# Sheet.net
KiCad netlist of a schematic drawn in Altium Designer
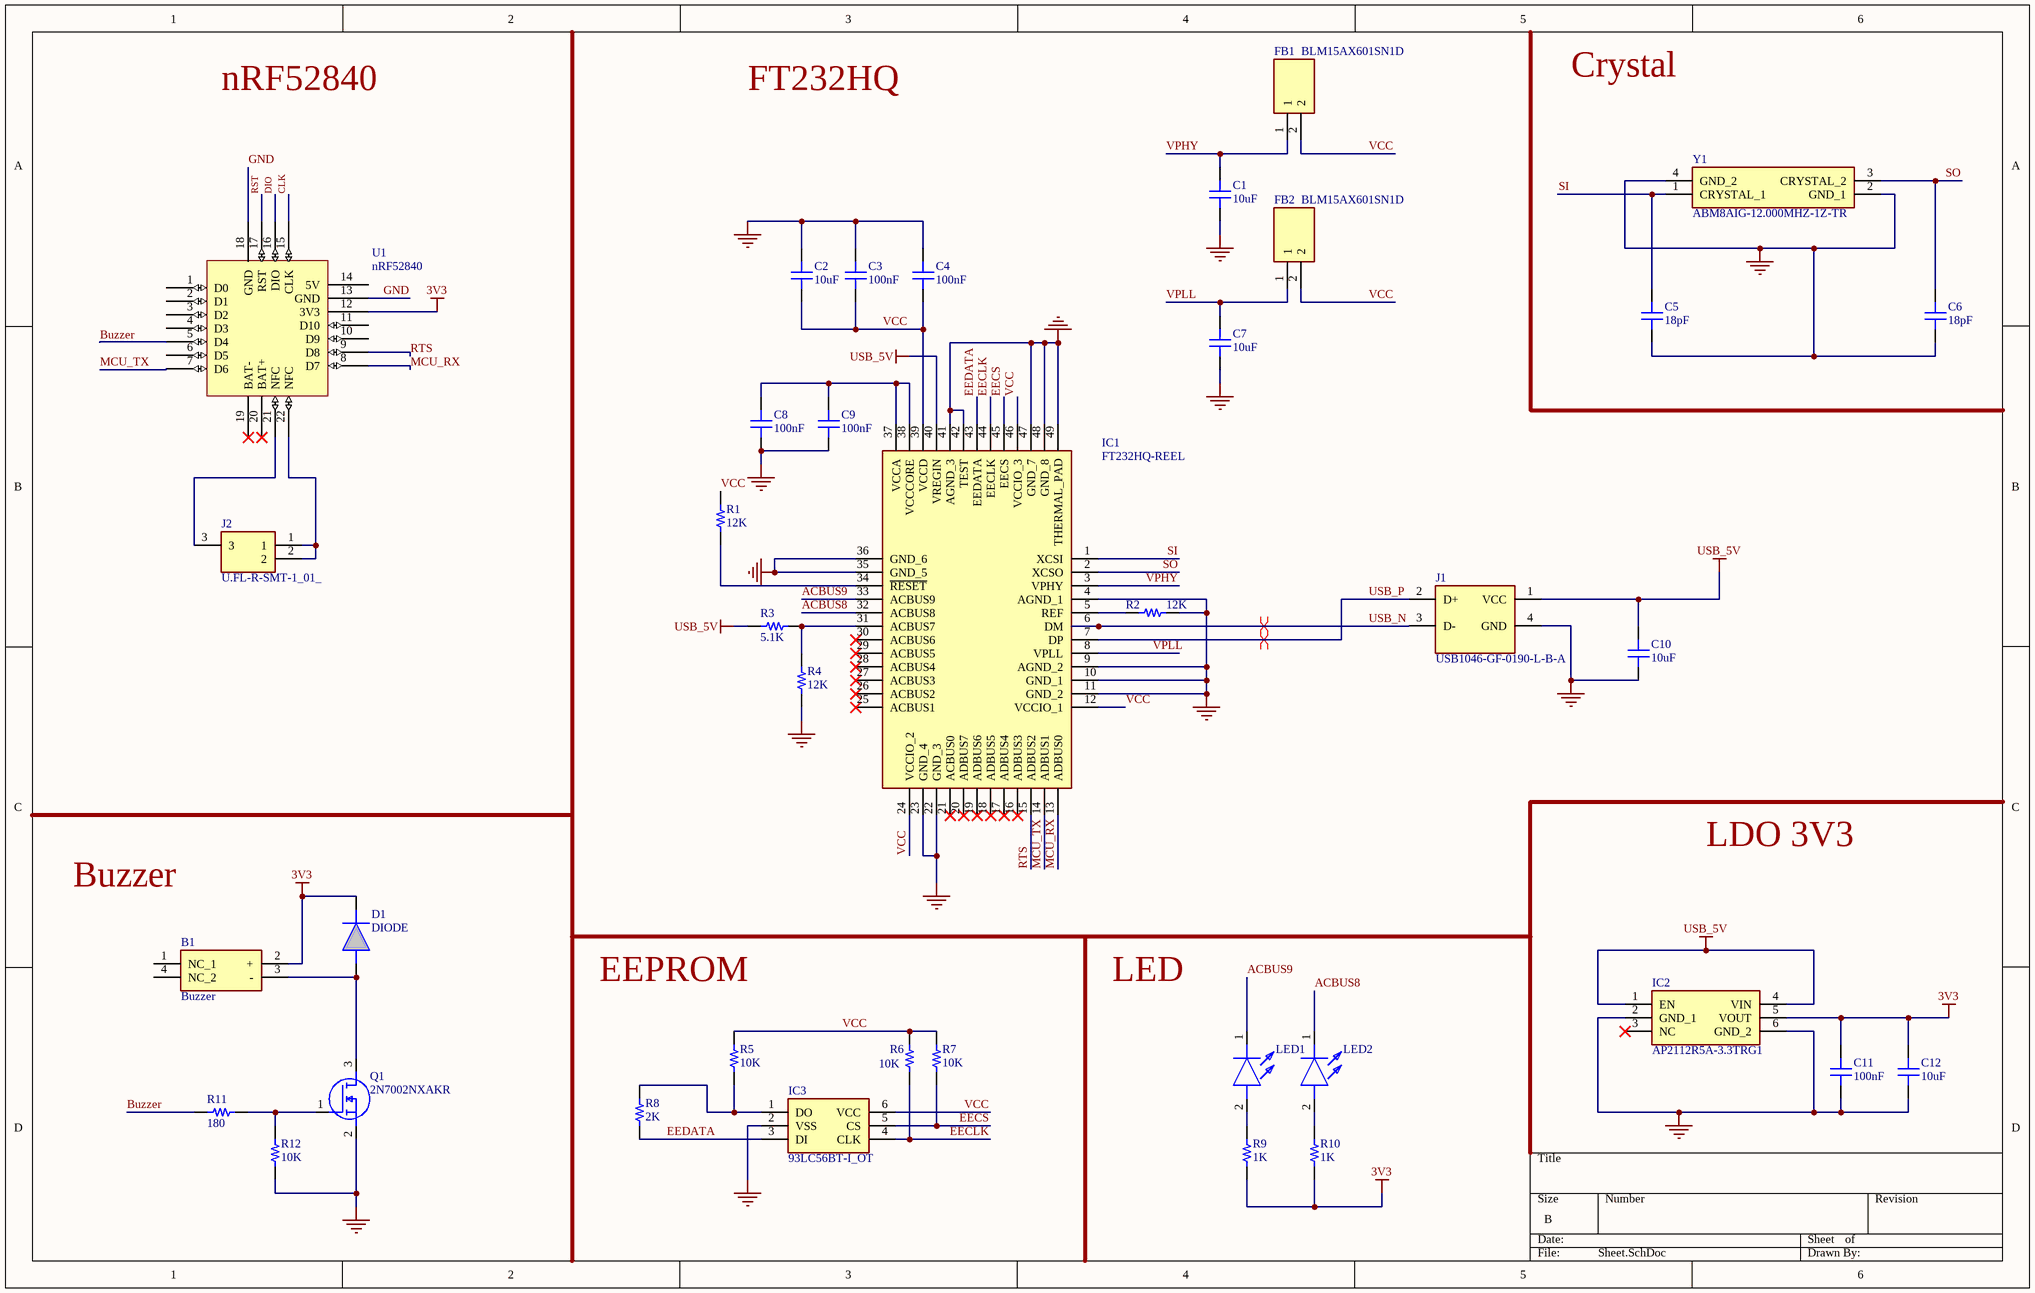
[diagram p0: Sheet.SchDoc]

(export (version "E")
  (design (tool "Eeschema 10.0.6"))
  (components
    (comp (ref "B1")
      (value "Buzzer")
      (footprint "CMT8530SSMTTR")
      (description "Speakers & Transducers Buzzer 8.5mm sq 2.73kHz 3.6V SMT")
      (fields
        (field (name "MOUSER PART NUMBER") "490-CMT-8530S-SMT-TR")
        (field (name "MANUFACTURER_PART_NUMBER") "CMT-8530S-SMT-TR")
      )
      (libsource (lib "Schlib1") (part "CMT-8530S-SMT-TR"))
    )
    (comp (ref "C1")
      (value "10uF")
      (footprint "CAP 0402_1005")
      (libsource (lib "MyAltiumLibs") (part "Cap 0402"))
    )
    (comp (ref "C2")
      (value "10uF")
      (footprint "CAP 0402_1005")
      (libsource (lib "MyAltiumLibs") (part "Cap 0402"))
    )
    (comp (ref "C3")
      (value "100nF")
      (footprint "CAP 0402_1005")
      (description "Multilayer Ceramic Capacitors MLCC - SMD/SMT 0402 16VDC 100nF 10% X7R")
      (libsource (lib "MyAltiumLibs") (part "Cap 0402"))
    )
    (comp (ref "C4")
      (value "100nF")
      (footprint "CAP 0402_1005")
      (description "Multilayer Ceramic Capacitors MLCC - SMD/SMT 0402 16VDC 100nF 10% X7R")
      (libsource (lib "MyAltiumLibs") (part "Cap 0402"))
    )
    (comp (ref "C5")
      (value "18pF")
      (footprint "CAP 0402_1005")
      (description "Multilayer Ceramic Capacitors MLCC - SMD/SMT 16V 18pF X8R 0402 2% AEC-Q200")
      (libsource (lib "MyAltiumLibs") (part "Cap 0402"))
    )
    (comp (ref "C6")
      (value "18pF")
      (footprint "CAP 0402_1005")
      (description "Multilayer Ceramic Capacitors MLCC - SMD/SMT 16V 18pF X8R 0402 2% AEC-Q200")
      (libsource (lib "MyAltiumLibs") (part "Cap 0402"))
    )
    (comp (ref "C7")
      (value "10uF")
      (footprint "CAP 0402_1005")
      (libsource (lib "MyAltiumLibs") (part "Cap 0402"))
    )
    (comp (ref "C8")
      (value "100nF")
      (footprint "CAP 0402_1005")
      (description "Multilayer Ceramic Capacitors MLCC - SMD/SMT 0402 16VDC 100nF 10% X7R")
      (libsource (lib "MyAltiumLibs") (part "Cap 0402"))
    )
    (comp (ref "C9")
      (value "100nF")
      (footprint "CAP 0402_1005")
      (description "Multilayer Ceramic Capacitors MLCC - SMD/SMT 0402 16VDC 100nF 10% X7R")
      (libsource (lib "MyAltiumLibs") (part "Cap 0402"))
    )
    (comp (ref "C10")
      (value "10uF")
      (footprint "CAP 0402_1005")
      (libsource (lib "MyAltiumLibs") (part "Cap 0402"))
    )
    (comp (ref "C11")
      (value "100nF")
      (footprint "CAP 0402_1005")
      (description "Multilayer Ceramic Capacitors MLCC - SMD/SMT 0402 16VDC 100nF 10% X7R")
      (libsource (lib "MyAltiumLibs") (part "Cap 0402"))
    )
    (comp (ref "C12")
      (value "10uF")
      (footprint "CAP 0402_1005")
      (libsource (lib "MyAltiumLibs") (part "Cap 0402"))
    )
    (comp (ref "D1")
      (value "DIODE")
      (footprint "SODFL1608X65N")
      (description "Rectifiers DIODE LOW LEAKAGE TAPE-7")
      (fields
        (field (name "MOUSER PART NUMBER") "771-BAS716-T/R")
        (field (name "MANUFACTURER_PART_NUMBER") "BAS716,115")
      )
      (libsource (lib "Schlib1") (part "BAS716_115"))
    )
    (comp (ref "FB1")
      (value "BLM15AX601SN1D")
      (footprint "GoldFinger_PcbLib:NFZ15SG152SN10B")
      (description "Ferrite Bead")
      (fields (field (name "MOUSER PART NUMBER") "81-BLM15AX601SN1D"))
      (libsource (lib "*") (part "BLM15AX601SN1D"))
    )
    (comp (ref "FB2")
      (value "BLM15AX601SN1D")
      (footprint "GoldFinger_PcbLib:NFZ15SG152SN10B")
      (description "Ferrite Bead")
      (fields (field (name "MOUSER PART NUMBER") "81-BLM15AX601SN1D"))
      (libsource (lib "*") (part "BLM15AX601SN1D"))
    )
    (comp (ref "IC1")
      (value "FT232HQ-REEL")
      (footprint "GoldFinger_PcbLib:QFN50P800X800X100-49N-D")
      (description "Integrated Circuit")
      (fields (field (name "MOUSER PART NUMBER") "895-FT232HQ-REEL"))
      (libsource (lib "*") (part "FT232HQ-REEL"))
    )
    (comp (ref "IC2")
      (value "AP2112R5A-3.3TRG1")
      (footprint "GoldFinger_PcbLib:AP2112R5A33TRG1")
      (description "Integrated Circuit")
      (fields (field (name "MOUSER PART NUMBER") "621-AP2112R5A-3.3TRG"))
      (libsource (lib "*") (part "AP2112R5A-3.3TRG1"))
    )
    (comp (ref "IC3")
      (value "93LC56BT-I_OT")
      (footprint "GoldFinger_PcbLib:SOT95P270X145-6N")
      (description "Integrated Circuit")
      (fields
        (field (name "MANUFACTURER_PART_NUMBER") "93LC56BT-I/OT")
        (field (name "MOUSER PART NUMBER") "579-93LC56BT-I/OT")
      )
      (libsource (lib "*") (part "93LC56BT-I_OT"))
    )
    (comp (ref "J1")
      (value "USB1046-GF-0190-L-B-A")
      (footprint "GoldFinger_PcbLib:USB1046GF0190LBA")
      (description "Connector")
      (fields (field (name "MOUSER PART NUMBER") "640-USB1046GF0190LBA"))
      (libsource (lib "GoldFinger_Schlib") (part "USB1046-GF-0190-L-B-A"))
    )
    (comp (ref "J2")
      (value "U.FL-R-SMT-1_01_")
      (footprint "GoldFinger_PcbLib:U.FL-R-SMT(01)")
      (description "Connector")
      (fields
        (field (name "MANUFACTURER_PART_NUMBER") "U.FL-R-SMT-1(01)")
        (field (name "MOUSER PART NUMBER") "798-UFLRSMT101")
      )
      (libsource (lib "*") (part "U.FL-R-SMT-1_01_"))
    )
    (comp (ref "LED1")
      (value "150040VS73240")
      (footprint "GoldFinger_PcbLib:LEDC1005X50N")
      (description "LED")
      (fields (field (name "MOUSER PART NUMBER") "710-150040VS73240"))
      (libsource (lib "*") (part "150040VS73240"))
    )
    (comp (ref "LED2")
      (value "LW_QH8G-Q2OO-3K5L-1")
      (footprint "GoldFinger_PcbLib:LEDC1005X40N")
      (description "LED")
      (fields
        (field (name "MANUFACTURER_PART_NUMBER") "LW QH8G-Q2OO-3K5L-1")
        (field (name "MOUSER PART NUMBER") "720-LWQH8G-Q2S2-3K5L")
      )
      (libsource (lib "*") (part "LW_QH8G-Q2OO-3K5L-1"))
    )
    (comp (ref "Q1")
      (value "2N7002NXAKR")
      (footprint "GoldFinger_PcbLib:SOT95P230X110-3N")
      (description "MOSFET (N-Channel)")
      (fields (field (name "MOUSER PART NUMBER") "771-2N7002NXAKR"))
      (libsource (lib "*") (part "2N7002NXAKR"))
    )
    (comp (ref "R1")
      (value "12K")
      (footprint "RES 0402_1005")
      (description "Thin Film Resistors - SMD 12kOhm,0402,1%,50ppm ,63mW,50V")
      (libsource (lib "MyAltiumLibs") (part "Res 0402"))
    )
    (comp (ref "R2")
      (value "12K")
      (footprint "RES 0402_1005")
      (description "Thin Film Resistors - SMD 12kOhm,0402,1%,50ppm ,63mW,50V")
      (libsource (lib "MyAltiumLibs") (part "Res 0402"))
    )
    (comp (ref "R3")
      (value "5.1K")
      (footprint "RES 0402_1005")
      (description "Thin Film Resistors - SMD 5.1K OHM 1% 50PPM 1/16W")
      (libsource (lib "MyAltiumLibs") (part "Res 0402"))
    )
    (comp (ref "R4")
      (value "12K")
      (footprint "RES 0402_1005")
      (description "Thin Film Resistors - SMD 12kOhm,0402,1%,50ppm ,63mW,50V")
      (libsource (lib "MyAltiumLibs") (part "Res 0402"))
    )
    (comp (ref "R5")
      (value "10K")
      (footprint "RES 0402_1005")
      (description "Thin Film Resistors - SMD 0402 10kOhms 1 % 50P PM 62.5mW AECQ200")
      (libsource (lib "MyAltiumLibs") (part "Res 0402"))
    )
    (comp (ref "R6")
      (value "10K")
      (footprint "RES 0402_1005")
      (description "Thin Film Resistors - SMD 0402 10kOhms 1 % 50P PM 62.5mW AECQ200")
      (libsource (lib "MyAltiumLibs") (part "Res 0402"))
    )
    (comp (ref "R7")
      (value "10K")
      (footprint "RES 0402_1005")
      (description "Thin Film Resistors - SMD 0402 10kOhms 1 % 50P PM 62.5mW AECQ200")
      (libsource (lib "MyAltiumLibs") (part "Res 0402"))
    )
    (comp (ref "R8")
      (value "2K")
      (footprint "RES 0402_1005")
      (description "Thin Film Resistors - SMD 0402 2.0Kohm .5% AEC-Q200")
      (libsource (lib "MyAltiumLibs") (part "Res 0402"))
    )
    (comp (ref "R9")
      (value "1K")
      (footprint "RES 0402_1005")
      (description "Thin Film Resistors - SMD 1K ohm 1% 1/16W")
      (libsource (lib "MyAltiumLibs") (part "Res 0402"))
    )
    (comp (ref "R10")
      (value "1K")
      (footprint "RES 0402_1005")
      (description "Thin Film Resistors - SMD 1K ohm 1% 1/16W")
      (libsource (lib "MyAltiumLibs") (part "Res 0402"))
    )
    (comp (ref "R11")
      (value "180")
      (footprint "RES 0402_1005")
      (description "Thin Film Resistors - SMD 0402 10kOhms 1 % 50P PM 62.5mW AECQ200")
      (libsource (lib "MyAltiumLibs") (part "Res 0402"))
    )
    (comp (ref "R12")
      (value "10K")
      (footprint "RES 0402_1005")
      (description "Thin Film Resistors - SMD 0402 10kOhms 1 % 50P PM 62.5mW AECQ200")
      (libsource (lib "MyAltiumLibs") (part "Res 0402"))
    )
    (comp (ref "U1")
      (value "nRF52840")
      (footprint "XIAO_nRF52840")
      (libsource (lib "GoldFinger_Schlib") (part "XIAO nRF52840"))
    )
    (comp (ref "Y1")
      (value "ABM8AIG-12.000MHZ-1Z-TR")
      (footprint "GoldFinger_PcbLib:ABM8AIG12000MHZ1ZTR")
      (description "Crystals AEC-Q200 CRYSTAL 12.000MHZ 18PF SMD")
      (fields (field (name "MOUSER PART NUMBER") "815-M8AIG-12-1ZT"))
      (libsource (lib "*") (part "ABM8AIG-12.000MHZ-1Z-TR"))
    )
  )
  (nets
    (net (code "1") (name "/ACBUS8") (class "Default")
      (node (ref "IC1") (pin "32") (pinfunction "ACBUS8_32") (pintype "passive"))
      (node (ref "LED2") (pin "1") (pinfunction "K_1") (pintype "passive"))
    )
    (net (code "2") (name "/ACBUS9") (class "Default")
      (node (ref "IC1") (pin "33") (pinfunction "ACBUS9_33") (pintype "passive"))
      (node (ref "LED1") (pin "1") (pinfunction "K_1") (pintype "passive"))
    )
    (net (code "3") (name "/Buzzer") (class "Default")
      (node (ref "R11") (pin "2") (pinfunction "2_2") (pintype "passive"))
      (node (ref "U1") (pin "5") (pinfunction "D4_5") (pintype "bidirectional"))
    )
    (net (code "4") (name "/CLK") (class "Default")
      (node (ref "U1") (pin "15") (pinfunction "CLK_15") (pintype "bidirectional"))
    )
    (net (code "5") (name "/DIO") (class "Default")
      (node (ref "U1") (pin "16") (pinfunction "DIO_16") (pintype "bidirectional"))
    )
    (net (code "6") (name "/EECLK") (class "Default")
      (node (ref "IC1") (pin "44") (pinfunction "EECLK_44") (pintype "passive"))
      (node (ref "IC3") (pin "4") (pinfunction "CLK_4") (pintype "passive"))
      (node (ref "R6") (pin "1") (pinfunction "1_1") (pintype "passive"))
    )
    (net (code "7") (name "/EECS") (class "Default")
      (node (ref "IC1") (pin "45") (pinfunction "EECS_45") (pintype "passive"))
      (node (ref "IC3") (pin "5") (pinfunction "CS_5") (pintype "passive"))
      (node (ref "R7") (pin "1") (pinfunction "1_1") (pintype "passive"))
    )
    (net (code "8") (name "/EEDATA") (class "Default")
      (node (ref "IC1") (pin "43") (pinfunction "EEDATA_43") (pintype "passive"))
      (node (ref "IC3") (pin "3") (pinfunction "DI_3") (pintype "passive"))
      (node (ref "R8") (pin "1") (pinfunction "1_1") (pintype "passive"))
    )
    (net (code "9") (name "/MCU_RX") (class "Default")
      (node (ref "IC1") (pin "13") (pinfunction "ADBUS0_13") (pintype "passive"))
      (node (ref "U1") (pin "8") (pinfunction "D7_8") (pintype "bidirectional"))
    )
    (net (code "10") (name "/MCU_TX") (class "Default")
      (node (ref "IC1") (pin "14") (pinfunction "ADBUS1_14") (pintype "passive"))
      (node (ref "U1") (pin "7") (pinfunction "D6_7") (pintype "bidirectional"))
    )
    (net (code "11") (name "/RST") (class "Default")
      (node (ref "U1") (pin "17") (pinfunction "RST_17") (pintype "bidirectional"))
    )
    (net (code "12") (name "/RTS") (class "Default")
      (node (ref "IC1") (pin "15") (pinfunction "ADBUS2_15") (pintype "passive"))
      (node (ref "U1") (pin "9") (pinfunction "D8_9") (pintype "bidirectional"))
    )
    (net (code "13") (name "/SI") (class "Default")
      (node (ref "C5") (pin "2") (pinfunction "2_2") (pintype "passive"))
      (node (ref "IC1") (pin "1") (pinfunction "XCSI_1") (pintype "passive"))
      (node (ref "Y1") (pin "1") (pinfunction "CRYSTAL_1_1") (pintype "passive"))
    )
    (net (code "14") (name "/SO") (class "Default")
      (node (ref "C6") (pin "2") (pinfunction "2_2") (pintype "passive"))
      (node (ref "IC1") (pin "2") (pinfunction "XCSO_2") (pintype "passive"))
      (node (ref "Y1") (pin "3") (pinfunction "CRYSTAL_2_3") (pintype "passive"))
    )
    (net (code "15") (name "/USB_N") (class "Default")
      (node (ref "IC1") (pin "6") (pinfunction "DM_6") (pintype "passive"))
      (node (ref "J1") (pin "3") (pinfunction "D-_3") (pintype "passive"))
    )
    (net (code "16") (name "/USB_P") (class "Default")
      (node (ref "IC1") (pin "7") (pinfunction "DP_7") (pintype "passive"))
      (node (ref "J1") (pin "2") (pinfunction "D+_2") (pintype "passive"))
    )
    (net (code "17") (name "/VCC") (class "Default")
      (node (ref "C2") (pin "1") (pinfunction "1_1") (pintype "passive"))
      (node (ref "C3") (pin "1") (pinfunction "1_1") (pintype "passive"))
      (node (ref "C4") (pin "1") (pinfunction "1_1") (pintype "passive"))
      (node (ref "FB1") (pin "2") (pinfunction "2_2") (pintype "passive"))
      (node (ref "FB2") (pin "2") (pinfunction "2_2") (pintype "passive"))
      (node (ref "IC1") (pin "12") (pinfunction "VCCIO_1_12") (pintype "passive"))
      (node (ref "IC1") (pin "24") (pinfunction "VCCIO_2_24") (pintype "passive"))
      (node (ref "IC1") (pin "39") (pinfunction "VCCD_39") (pintype "passive"))
      (node (ref "IC1") (pin "46") (pinfunction "VCCIO_3_46") (pintype "passive"))
      (node (ref "IC3") (pin "6") (pinfunction "VCC_6") (pintype "passive"))
      (node (ref "R1") (pin "2") (pinfunction "2_2") (pintype "passive"))
      (node (ref "R5") (pin "2") (pinfunction "2_2") (pintype "passive"))
      (node (ref "R6") (pin "2") (pinfunction "2_2") (pintype "passive"))
      (node (ref "R7") (pin "2") (pinfunction "2_2") (pintype "passive"))
    )
    (net (code "18") (name "/VPHY") (class "Default")
      (node (ref "C1") (pin "2") (pinfunction "2_2") (pintype "passive"))
      (node (ref "FB1") (pin "1") (pinfunction "1_1") (pintype "passive"))
      (node (ref "IC1") (pin "3") (pinfunction "VPHY_3") (pintype "passive"))
    )
    (net (code "19") (name "/VPLL") (class "Default")
      (node (ref "C7") (pin "2") (pinfunction "2_2") (pintype "passive"))
      (node (ref "FB2") (pin "1") (pinfunction "1_1") (pintype "passive"))
      (node (ref "IC1") (pin "8") (pinfunction "VPLL_8") (pintype "passive"))
    )
    (net (code "20") (name "3V3") (class "Default")
      (node (ref "B1") (pin "2") (pinfunction "+_2") (pintype "passive"))
      (node (ref "C11") (pin "2") (pinfunction "2_2") (pintype "passive"))
      (node (ref "C12") (pin "2") (pinfunction "2_2") (pintype "passive"))
      (node (ref "D1") (pin "1") (pinfunction "K_1") (pintype "passive"))
      (node (ref "IC2") (pin "5") (pinfunction "VOUT_5") (pintype "passive"))
      (node (ref "R10") (pin "1") (pinfunction "1_1") (pintype "passive"))
      (node (ref "R9") (pin "1") (pinfunction "1_1") (pintype "passive"))
      (node (ref "U1") (pin "12") (pinfunction "3V3_12") (pintype "power_in"))
    )
    (net (code "21") (name "GND") (class "Default")
      (node (ref "C1") (pin "1") (pinfunction "1_1") (pintype "passive"))
      (node (ref "C10") (pin "1") (pinfunction "1_1") (pintype "passive"))
      (node (ref "C11") (pin "1") (pinfunction "1_1") (pintype "passive"))
      (node (ref "C12") (pin "1") (pinfunction "1_1") (pintype "passive"))
      (node (ref "C2") (pin "2") (pinfunction "2_2") (pintype "passive"))
      (node (ref "C3") (pin "2") (pinfunction "2_2") (pintype "passive"))
      (node (ref "C4") (pin "2") (pinfunction "2_2") (pintype "passive"))
      (node (ref "C5") (pin "1") (pinfunction "1_1") (pintype "passive"))
      (node (ref "C6") (pin "1") (pinfunction "1_1") (pintype "passive"))
      (node (ref "C7") (pin "1") (pinfunction "1_1") (pintype "passive"))
      (node (ref "C8") (pin "1") (pinfunction "1_1") (pintype "passive"))
      (node (ref "C9") (pin "1") (pinfunction "1_1") (pintype "passive"))
      (node (ref "IC1") (pin "10") (pinfunction "GND_1_10") (pintype "passive"))
      (node (ref "IC1") (pin "11") (pinfunction "GND_2_11") (pintype "passive"))
      (node (ref "IC1") (pin "22") (pinfunction "GND_3_22") (pintype "passive"))
      (node (ref "IC1") (pin "23") (pinfunction "GND_4_23") (pintype "passive"))
      (node (ref "IC1") (pin "35") (pinfunction "GND_5_35") (pintype "passive"))
      (node (ref "IC1") (pin "36") (pinfunction "GND_6_36") (pintype "passive"))
      (node (ref "IC1") (pin "4") (pinfunction "AGND_1_4") (pintype "passive"))
      (node (ref "IC1") (pin "41") (pinfunction "AGND_3_41") (pintype "passive"))
      (node (ref "IC1") (pin "42") (pinfunction "TEST_42") (pintype "passive"))
      (node (ref "IC1") (pin "47") (pinfunction "GND_7_47") (pintype "passive"))
      (node (ref "IC1") (pin "48") (pinfunction "GND_8_48") (pintype "passive"))
      (node (ref "IC1") (pin "49") (pinfunction "THERMAL_PAD_49") (pintype "passive"))
      (node (ref "IC1") (pin "9") (pinfunction "AGND_2_9") (pintype "passive"))
      (node (ref "IC2") (pin "2") (pinfunction "GND_1_2") (pintype "passive"))
      (node (ref "IC2") (pin "6") (pinfunction "GND_2_6") (pintype "passive"))
      (node (ref "IC3") (pin "2") (pinfunction "VSS_2") (pintype "passive"))
      (node (ref "J1") (pin "4") (pinfunction "GND_4") (pintype "passive"))
      (node (ref "Q1") (pin "2") (pinfunction "S_2") (pintype "passive"))
      (node (ref "R12") (pin "1") (pinfunction "1_1") (pintype "passive"))
      (node (ref "R2") (pin "1") (pinfunction "1_1") (pintype "passive"))
      (node (ref "R4") (pin "1") (pinfunction "1_1") (pintype "passive"))
      (node (ref "U1") (pin "13") (pinfunction "GND_13") (pintype "power_in"))
      (node (ref "U1") (pin "18") (pinfunction "GND_18") (pintype "power_in"))
      (node (ref "Y1") (pin "2") (pinfunction "GND_1_2") (pintype "passive"))
      (node (ref "Y1") (pin "4") (pinfunction "GND_2_4") (pintype "passive"))
    )
    (net (code "22") (name "Net-(B1--)") (class "Default")
      (node (ref "B1") (pin "3") (pinfunction "-_3") (pintype "passive"))
      (node (ref "D1") (pin "2") (pinfunction "A_2") (pintype "passive"))
      (node (ref "Q1") (pin "3") (pinfunction "D_3") (pintype "passive"))
    )
    (net (code "23") (name "Net-(IC1-ACBUS7)") (class "Default")
      (node (ref "IC1") (pin "31") (pinfunction "ACBUS7_31") (pintype "passive"))
      (node (ref "R3") (pin "1") (pinfunction "1_1") (pintype "passive"))
      (node (ref "R4") (pin "2") (pinfunction "2_2") (pintype "passive"))
    )
    (net (code "24") (name "Net-(IC1-REF)") (class "Default")
      (node (ref "IC1") (pin "5") (pinfunction "REF_5") (pintype "passive"))
      (node (ref "R2") (pin "2") (pinfunction "2_2") (pintype "passive"))
    )
    (net (code "25") (name "Net-(IC1-VCCA)") (class "Default")
      (node (ref "C8") (pin "2") (pinfunction "2_2") (pintype "passive"))
      (node (ref "C9") (pin "2") (pinfunction "2_2") (pintype "passive"))
      (node (ref "IC1") (pin "37") (pinfunction "VCCA_37") (pintype "passive"))
      (node (ref "IC1") (pin "38") (pinfunction "VCCCORE_38") (pintype "passive"))
    )
    (net (code "26") (name "Net-(IC1-~{RESET})") (class "Default")
      (node (ref "IC1") (pin "34") (pinfunction "~{RESET}_34") (pintype "passive"))
      (node (ref "R1") (pin "1") (pinfunction "1_1") (pintype "passive"))
    )
    (net (code "27") (name "Net-(IC3-DO)") (class "Default")
      (node (ref "IC3") (pin "1") (pinfunction "DO_1") (pintype "passive"))
      (node (ref "R5") (pin "1") (pinfunction "1_1") (pintype "passive"))
      (node (ref "R8") (pin "2") (pinfunction "2_2") (pintype "passive"))
    )
    (net (code "28") (name "Net-(J2-Pad1)") (class "Default")
      (node (ref "J2") (pin "1") (pinfunction "1_1") (pintype "passive"))
      (node (ref "J2") (pin "2") (pinfunction "2_2") (pintype "passive"))
      (node (ref "U1") (pin "22") (pinfunction "NFC_22") (pintype "bidirectional"))
    )
    (net (code "29") (name "Net-(J2-Pad3)") (class "Default")
      (node (ref "J2") (pin "3") (pinfunction "3_3") (pintype "passive"))
      (node (ref "U1") (pin "21") (pinfunction "NFC_21") (pintype "bidirectional"))
    )
    (net (code "30") (name "Net-(LED1-A)") (class "Default")
      (node (ref "LED1") (pin "2") (pinfunction "A_2") (pintype "passive"))
      (node (ref "R9") (pin "2") (pinfunction "2_2") (pintype "passive"))
    )
    (net (code "31") (name "Net-(LED2-A)") (class "Default")
      (node (ref "LED2") (pin "2") (pinfunction "A_2") (pintype "passive"))
      (node (ref "R10") (pin "2") (pinfunction "2_2") (pintype "passive"))
    )
    (net (code "32") (name "Net-(Q1-G)") (class "Default")
      (node (ref "Q1") (pin "1") (pinfunction "G_1") (pintype "passive"))
      (node (ref "R11") (pin "1") (pinfunction "1_1") (pintype "passive"))
      (node (ref "R12") (pin "2") (pinfunction "2_2") (pintype "passive"))
    )
    (net (code "33") (name "USB_5V") (class "Default")
      (node (ref "C10") (pin "2") (pinfunction "2_2") (pintype "passive"))
      (node (ref "IC1") (pin "40") (pinfunction "VREGIN_40") (pintype "passive"))
      (node (ref "IC2") (pin "1") (pinfunction "EN_1") (pintype "passive"))
      (node (ref "IC2") (pin "4") (pinfunction "VIN_4") (pintype "passive"))
      (node (ref "J1") (pin "1") (pinfunction "VCC_1") (pintype "passive"))
      (node (ref "R3") (pin "2") (pinfunction "2_2") (pintype "passive"))
    )
    (net (code "34") (name "unconnected-(B1-NC_1-Pad1)") (class "Default")
      (node (ref "B1") (pin "1") (pinfunction "NC_1_1") (pintype "passive"))
    )
    (net (code "35") (name "unconnected-(B1-NC_2-Pad4)") (class "Default")
      (node (ref "B1") (pin "4") (pinfunction "NC_2_4") (pintype "passive"))
    )
    (net (code "36") (name "unconnected-(IC1-ACBUS0-Pad21)") (class "Default")
      (node (ref "IC1") (pin "21") (pinfunction "ACBUS0_21") (pintype "passive+no_connect"))
    )
    (net (code "37") (name "unconnected-(IC1-ACBUS1-Pad25)") (class "Default")
      (node (ref "IC1") (pin "25") (pinfunction "ACBUS1_25") (pintype "passive+no_connect"))
    )
    (net (code "38") (name "unconnected-(IC1-ACBUS2-Pad26)") (class "Default")
      (node (ref "IC1") (pin "26") (pinfunction "ACBUS2_26") (pintype "passive+no_connect"))
    )
    (net (code "39") (name "unconnected-(IC1-ACBUS3-Pad27)") (class "Default")
      (node (ref "IC1") (pin "27") (pinfunction "ACBUS3_27") (pintype "passive+no_connect"))
    )
    (net (code "40") (name "unconnected-(IC1-ACBUS4-Pad28)") (class "Default")
      (node (ref "IC1") (pin "28") (pinfunction "ACBUS4_28") (pintype "passive+no_connect"))
    )
    (net (code "41") (name "unconnected-(IC1-ACBUS5-Pad29)") (class "Default")
      (node (ref "IC1") (pin "29") (pinfunction "ACBUS5_29") (pintype "passive+no_connect"))
    )
    (net (code "42") (name "unconnected-(IC1-ACBUS6-Pad30)") (class "Default")
      (node (ref "IC1") (pin "30") (pinfunction "ACBUS6_30") (pintype "passive+no_connect"))
    )
    (net (code "43") (name "unconnected-(IC1-ADBUS3-Pad16)") (class "Default")
      (node (ref "IC1") (pin "16") (pinfunction "ADBUS3_16") (pintype "passive+no_connect"))
    )
    (net (code "44") (name "unconnected-(IC1-ADBUS4-Pad17)") (class "Default")
      (node (ref "IC1") (pin "17") (pinfunction "ADBUS4_17") (pintype "passive+no_connect"))
    )
    (net (code "45") (name "unconnected-(IC1-ADBUS5-Pad18)") (class "Default")
      (node (ref "IC1") (pin "18") (pinfunction "ADBUS5_18") (pintype "passive+no_connect"))
    )
    (net (code "46") (name "unconnected-(IC1-ADBUS6-Pad19)") (class "Default")
      (node (ref "IC1") (pin "19") (pinfunction "ADBUS6_19") (pintype "passive+no_connect"))
    )
    (net (code "47") (name "unconnected-(IC1-ADBUS7-Pad20)") (class "Default")
      (node (ref "IC1") (pin "20") (pinfunction "ADBUS7_20") (pintype "passive+no_connect"))
    )
    (net (code "48") (name "unconnected-(IC2-NC-Pad3)") (class "Default")
      (node (ref "IC2") (pin "3") (pinfunction "NC_3") (pintype "passive+no_connect"))
    )
    (net (code "49") (name "unconnected-(U1-5V-Pad14)") (class "Default")
      (node (ref "U1") (pin "14") (pinfunction "5V_14") (pintype "power_in"))
    )
    (net (code "50") (name "unconnected-(U1-BAT+-Pad20)") (class "Default")
      (node (ref "U1") (pin "20") (pinfunction "BAT+_20") (pintype "power_in+no_connect"))
    )
    (net (code "51") (name "unconnected-(U1-BAT--Pad19)") (class "Default")
      (node (ref "U1") (pin "19") (pinfunction "BAT-_19") (pintype "power_in+no_connect"))
    )
    (net (code "52") (name "unconnected-(U1-D0-Pad1)") (class "Default")
      (node (ref "U1") (pin "1") (pinfunction "D0_1") (pintype "bidirectional"))
    )
    (net (code "53") (name "unconnected-(U1-D1-Pad2)") (class "Default")
      (node (ref "U1") (pin "2") (pinfunction "D1_2") (pintype "bidirectional"))
    )
    (net (code "54") (name "unconnected-(U1-D2-Pad3)") (class "Default")
      (node (ref "U1") (pin "3") (pinfunction "D2_3") (pintype "bidirectional"))
    )
    (net (code "55") (name "unconnected-(U1-D3-Pad4)") (class "Default")
      (node (ref "U1") (pin "4") (pinfunction "D3_4") (pintype "bidirectional"))
    )
    (net (code "56") (name "unconnected-(U1-D5-Pad6)") (class "Default")
      (node (ref "U1") (pin "6") (pinfunction "D5_6") (pintype "bidirectional"))
    )
    (net (code "57") (name "unconnected-(U1-D9-Pad10)") (class "Default")
      (node (ref "U1") (pin "10") (pinfunction "D9_10") (pintype "bidirectional"))
    )
    (net (code "58") (name "unconnected-(U1-D10-Pad11)") (class "Default")
      (node (ref "U1") (pin "11") (pinfunction "D10_11") (pintype "bidirectional"))
    )
  )
)
